# sensor.net
KiCad netlist of a schematic drawn in Altium Designer
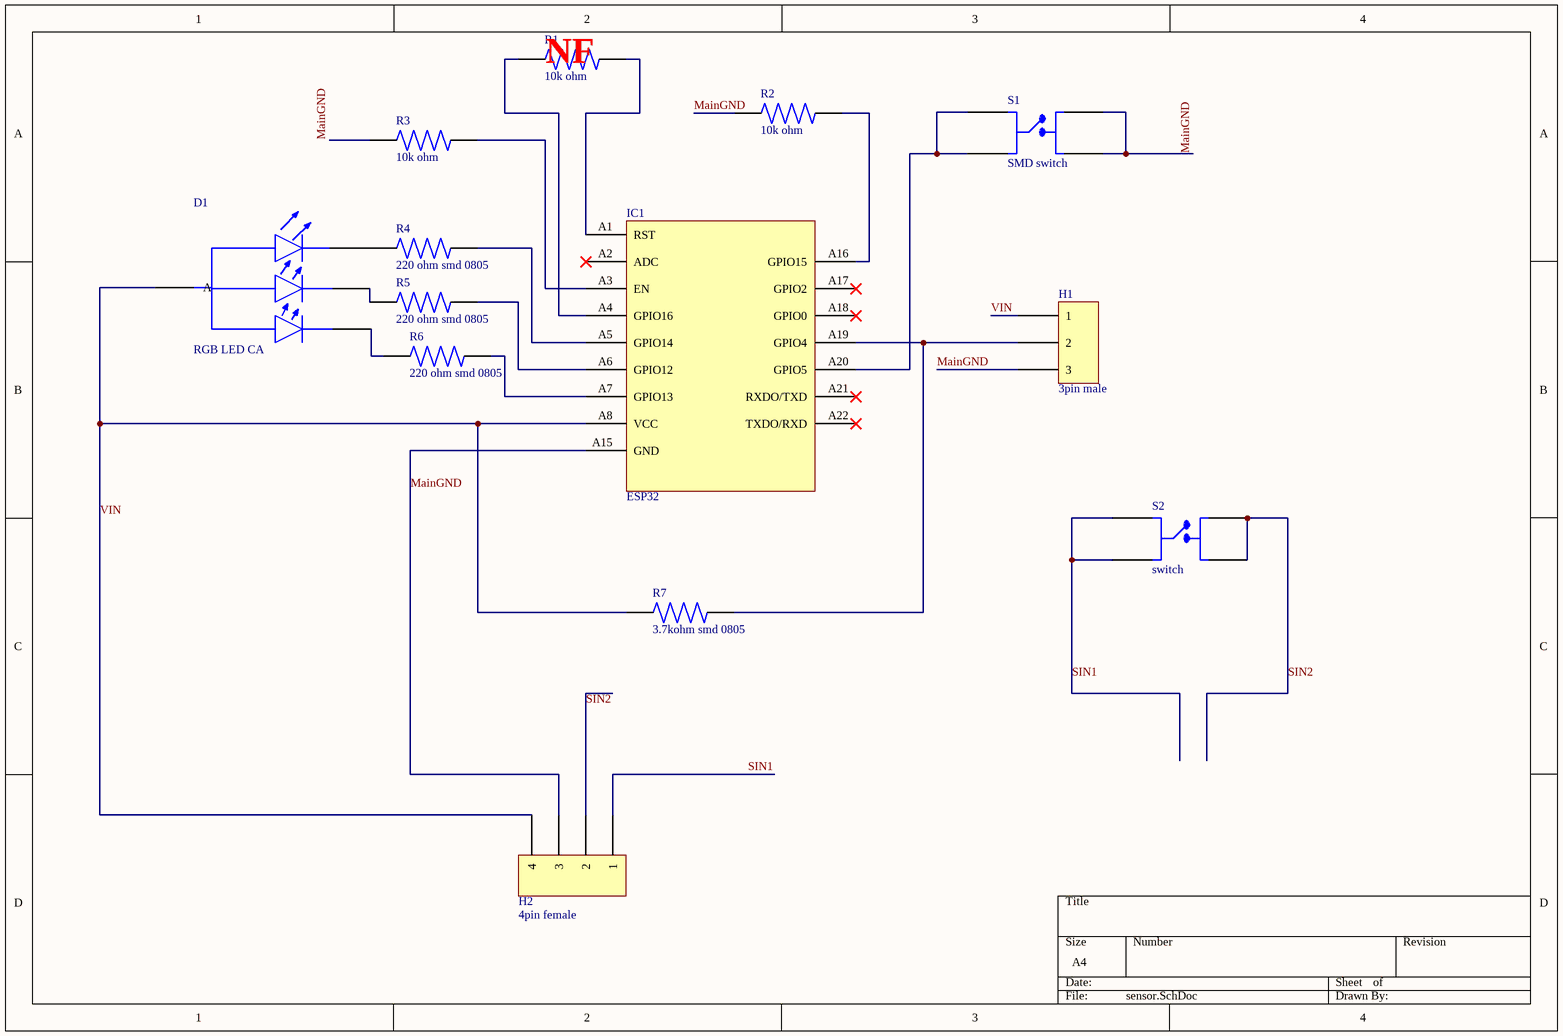
[diagram p0: sensor.SchDoc]

(export (version "E")
  (design (tool "Eeschema 10.0.6"))
  (components
    (comp (ref "D1")
      (value "RGB LED CA")
      (footprint "RGB LED")
      (description "Led Rgb, T-1 3/4, 5MM Round T/h,")
      (fields
        (field (name "MANUFACTURER") "QT-Brightek")
        (field (name "MANUFACTURER PART NUMBER") "QBL8RGB60D0-2897")
      )
      (libsource (lib "Project") (part "QBL8RGB60D0-2897"))
    )
    (comp (ref "H1")
      (value "3pin male")
      (footprint "3 pin Male header")
      (fields (field (name "MANUFACTURER") "Harwin") (field (name "MANUFACTURER PART NUMBER") "M20-9990345"))
      (libsource (lib "Project") (part "M20-9990345"))
    )
    (comp (ref "H2")
      (value "4pin female")
      (footprint "4pin female")
      (fields
        (field (name "MANUFACTURER") "Sullins")
        (field (name "MANUFACTURER PART NUMBER") "PPPC041LFBN-RC")
      )
      (libsource (lib "Project") (part "PPPC041LFBN-RC"))
    )
    (comp (ref "IC1")
      (value "ESP32")
      (footprint "ESP 32 12f")
      (description "Wi-fi, BLE5.0, 32 Bit Mcu Int Ant")
      (fields
        (field (name "MANUFACTURER") "RF Solutions")
        (field (name "MANUFACTURER PART NUMBER") "ESP32-C3-12F")
      )
      (libsource (lib "Project") (part "ESP32-C3-12F"))
    )
    (comp (ref "R1")
      (value "10k ohm")
      (footprint "0805 SMD")
      (fields
        (field (name "MANUFACTURER") "Stackpole Electronics")
        (field (name "MANUFACTURER PART NUMBER") "RMCF0805FT10K0")
        (field (name "TOLERANCE") "1%")
      )
      (libsource (lib "Project") (part "RMCF0805FT10K0"))
    )
    (comp (ref "R2")
      (value "10k ohm")
      (footprint "0805 SMD")
      (fields
        (field (name "MANUFACTURER") "Stackpole Electronics")
        (field (name "MANUFACTURER PART NUMBER") "RMCF0805FT10K0")
        (field (name "TOLERANCE") "1%")
      )
      (libsource (lib "Project") (part "RMCF0805FT10K0"))
    )
    (comp (ref "R3")
      (value "10k ohm")
      (footprint "0805 SMD")
      (fields
        (field (name "MANUFACTURER") "Stackpole Electronics")
        (field (name "MANUFACTURER PART NUMBER") "RMCF0805FT10K0")
        (field (name "TOLERANCE") "1%")
      )
      (libsource (lib "Project") (part "RMCF0805FT10K0"))
    )
    (comp (ref "R4")
      (value "220 ohm smd 0805")
      (footprint "0805 SMD")
      (fields
        (field (name "MANUFACTURER") "TE Connectivity")
        (field (name "MANUFACTURER PART NUMBER") "CRGCQ0805F220R")
      )
      (libsource (lib "Project") (part "CRGCQ0805F220R"))
    )
    (comp (ref "R5")
      (value "220 ohm smd 0805")
      (footprint "0805 SMD")
      (fields
        (field (name "MANUFACTURER") "TE Connectivity")
        (field (name "MANUFACTURER PART NUMBER") "CRGCQ0805F220R")
      )
      (libsource (lib "Project") (part "CRGCQ0805F220R"))
    )
    (comp (ref "R6")
      (value "220 ohm smd 0805")
      (footprint "0805 SMD")
      (fields
        (field (name "MANUFACTURER") "TE Connectivity")
        (field (name "MANUFACTURER PART NUMBER") "CRGCQ0805F220R")
      )
      (libsource (lib "Project") (part "CRGCQ0805F220R"))
    )
    (comp (ref "R7")
      (value "3.7kohm smd 0805")
      (footprint "0805 SMD")
      (description "Fixed Resistor, Thin Film, 0.125W, 3700ohm, 150V, 0.5% +/-Tol, 25ppm/Cel, Surface Mount, 0805")
      (fields
        (field (name "MANUFACTURER") "KOA Speer")
        (field (name "MANUFACTURER PART NUMBER") "RN73R2ATTD3701D25")
      )
      (libsource (lib "Project") (part "RN73R2ATTD3701D25"))
    )
    (comp (ref "S1")
      (value "SMD switch")
      (footprint "SOP127P600-8N")
      (description "Switch Tactile N.O. SPST Round Button Gull Wing 0.05A 12VDC 200000Cycles 2.45N SMD T/R")
      (fields
        (field (name "MANUFACTURER") "ITT C&K")
        (field (name "MANUFACTURER PART NUMBER") "PTS526SK15SMTR2LFS")
      )
      (libsource (lib "Project") (part "PTS526SK15SMTR2LFS"))
    )
    (comp (ref "S2")
      (value "switch")
      (footprint "SW_TS02-66-60-BK-260-LCR-D")
      (fields
        (field (name "MANUFACTURER") "TE Connectivity Alcoswitch")
        (field (name "MANUFACTURER PART NUMBER") "1825910-6")
      )
      (libsource (lib "Project") (part "1825910-6"))
    )
  )
  (nets
    (net (code "1") (name "/MainGND") (class "Default")
      (node (ref "H1") (pin "3") (pinfunction "3_3") (pintype "passive"))
      (node (ref "H2") (pin "3") (pinfunction "3_3") (pintype "passive"))
      (node (ref "IC1") (pin "A15") (pinfunction "GND_A15") (pintype "passive"))
      (node (ref "R2") (pin "1") (pinfunction "1_1") (pintype "passive"))
      (node (ref "R3") (pin "1") (pinfunction "1_1") (pintype "passive"))
      (node (ref "S1") (pin "3") (pinfunction "3_3") (pintype "passive"))
      (node (ref "S1") (pin "4") (pinfunction "4_4") (pintype "passive"))
    )
    (net (code "2") (name "/SIN1") (class "Default")
      (node (ref "H2") (pin "1") (pinfunction "1_1") (pintype "passive"))
      (node (ref "S2") (pin "1") (pinfunction "1_1") (pintype "passive"))
      (node (ref "S2") (pin "2") (pinfunction "2_2") (pintype "passive"))
    )
    (net (code "3") (name "/SIN2") (class "Default")
      (node (ref "H2") (pin "2") (pinfunction "2_2") (pintype "passive"))
      (node (ref "S2") (pin "3") (pinfunction "3_3") (pintype "passive"))
      (node (ref "S2") (pin "4") (pinfunction "4_4") (pintype "passive"))
    )
    (net (code "4") (name "/VIN") (class "Default")
      (node (ref "D1") (pin "2") (pinfunction "A_2") (pintype "passive"))
      (node (ref "H1") (pin "1") (pinfunction "1_1") (pintype "passive"))
      (node (ref "H2") (pin "4") (pinfunction "4_4") (pintype "passive"))
      (node (ref "IC1") (pin "A8") (pinfunction "VCC_A8") (pintype "passive"))
      (node (ref "R7") (pin "1") (pinfunction "1_1") (pintype "passive"))
    )
    (net (code "5") (name "Net-(D1-26)") (class "Default")
      (node (ref "D1") (pin "3") (pinfunction "26_3") (pintype "passive"))
      (node (ref "R5") (pin "1") (pinfunction "1_1") (pintype "passive"))
    )
    (net (code "6") (name "Net-(D1-27)") (class "Default")
      (node (ref "D1") (pin "4") (pinfunction "27_4") (pintype "passive"))
      (node (ref "R6") (pin "1") (pinfunction "1_1") (pintype "passive"))
    )
    (net (code "7") (name "Net-(D1-Pad1)") (class "Default")
      (node (ref "D1") (pin "1") (pinfunction "1_1") (pintype "passive"))
      (node (ref "R4") (pin "1") (pinfunction "1_1") (pintype "passive"))
    )
    (net (code "8") (name "Net-(IC1-EN)") (class "Default")
      (node (ref "IC1") (pin "A3") (pinfunction "EN_A3") (pintype "passive"))
      (node (ref "R3") (pin "2") (pinfunction "2_2") (pintype "passive"))
    )
    (net (code "9") (name "Net-(IC1-GPIO4)") (class "Default")
      (node (ref "H1") (pin "2") (pinfunction "2_2") (pintype "passive"))
      (node (ref "IC1") (pin "A19") (pinfunction "GPIO4_A19") (pintype "passive"))
      (node (ref "R7") (pin "2") (pinfunction "2_2") (pintype "passive"))
    )
    (net (code "10") (name "Net-(IC1-GPIO5)") (class "Default")
      (node (ref "IC1") (pin "A20") (pinfunction "GPIO5_A20") (pintype "passive"))
      (node (ref "S1") (pin "1") (pinfunction "1_1") (pintype "passive"))
      (node (ref "S1") (pin "2") (pinfunction "2_2") (pintype "passive"))
    )
    (net (code "11") (name "Net-(IC1-GPIO12)") (class "Default")
      (node (ref "IC1") (pin "A6") (pinfunction "GPIO12_A6") (pintype "passive"))
      (node (ref "R5") (pin "2") (pinfunction "2_2") (pintype "passive"))
    )
    (net (code "12") (name "Net-(IC1-GPIO13)") (class "Default")
      (node (ref "IC1") (pin "A7") (pinfunction "GPIO13_A7") (pintype "passive"))
      (node (ref "R6") (pin "2") (pinfunction "2_2") (pintype "passive"))
    )
    (net (code "13") (name "Net-(IC1-GPIO14)") (class "Default")
      (node (ref "IC1") (pin "A5") (pinfunction "GPIO14_A5") (pintype "passive"))
      (node (ref "R4") (pin "2") (pinfunction "2_2") (pintype "passive"))
    )
    (net (code "14") (name "Net-(IC1-GPIO15)") (class "Default")
      (node (ref "IC1") (pin "A16") (pinfunction "GPIO15_A16") (pintype "passive"))
      (node (ref "R2") (pin "2") (pinfunction "2_2") (pintype "passive"))
    )
    (net (code "15") (name "Net-(IC1-GPIO16)") (class "Default")
      (node (ref "IC1") (pin "A4") (pinfunction "GPIO16_A4") (pintype "passive"))
      (node (ref "R1") (pin "1") (pinfunction "1_1") (pintype "passive"))
    )
    (net (code "16") (name "Net-(IC1-RST)") (class "Default")
      (node (ref "IC1") (pin "A1") (pinfunction "RST_A1") (pintype "passive"))
      (node (ref "R1") (pin "2") (pinfunction "2_2") (pintype "passive"))
    )
    (net (code "17") (name "unconnected-(IC1-ADC-PadA2)") (class "Default")
      (node (ref "IC1") (pin "A2") (pinfunction "ADC_A2") (pintype "passive+no_connect"))
    )
    (net (code "18") (name "unconnected-(IC1-GPIO0-PadA18)") (class "Default")
      (node (ref "IC1") (pin "A18") (pinfunction "GPIO0_A18") (pintype "passive+no_connect"))
    )
    (net (code "19") (name "unconnected-(IC1-GPIO2-PadA17)") (class "Default")
      (node (ref "IC1") (pin "A17") (pinfunction "GPIO2_A17") (pintype "passive+no_connect"))
    )
    (net (code "20") (name "unconnected-(IC1-RXDO{slash}TXD-PadA21)") (class "Default")
      (node (ref "IC1") (pin "A21") (pinfunction "RXDO/TXD_A21") (pintype "passive+no_connect"))
    )
    (net (code "21") (name "unconnected-(IC1-TXDO{slash}RXD-PadA22)") (class "Default")
      (node (ref "IC1") (pin "A22") (pinfunction "TXDO/RXD_A22") (pintype "passive+no_connect"))
    )
  )
)
